# OSC.net
KiCad netlist of a schematic drawn in EAGLE
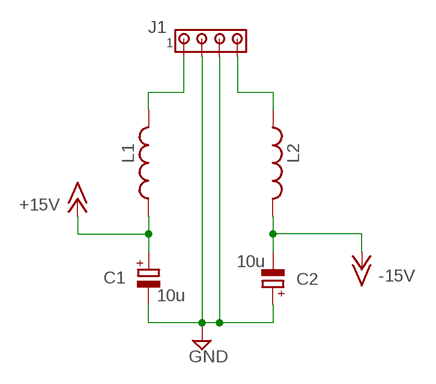
[diagram p0: schematic, sheet 1]
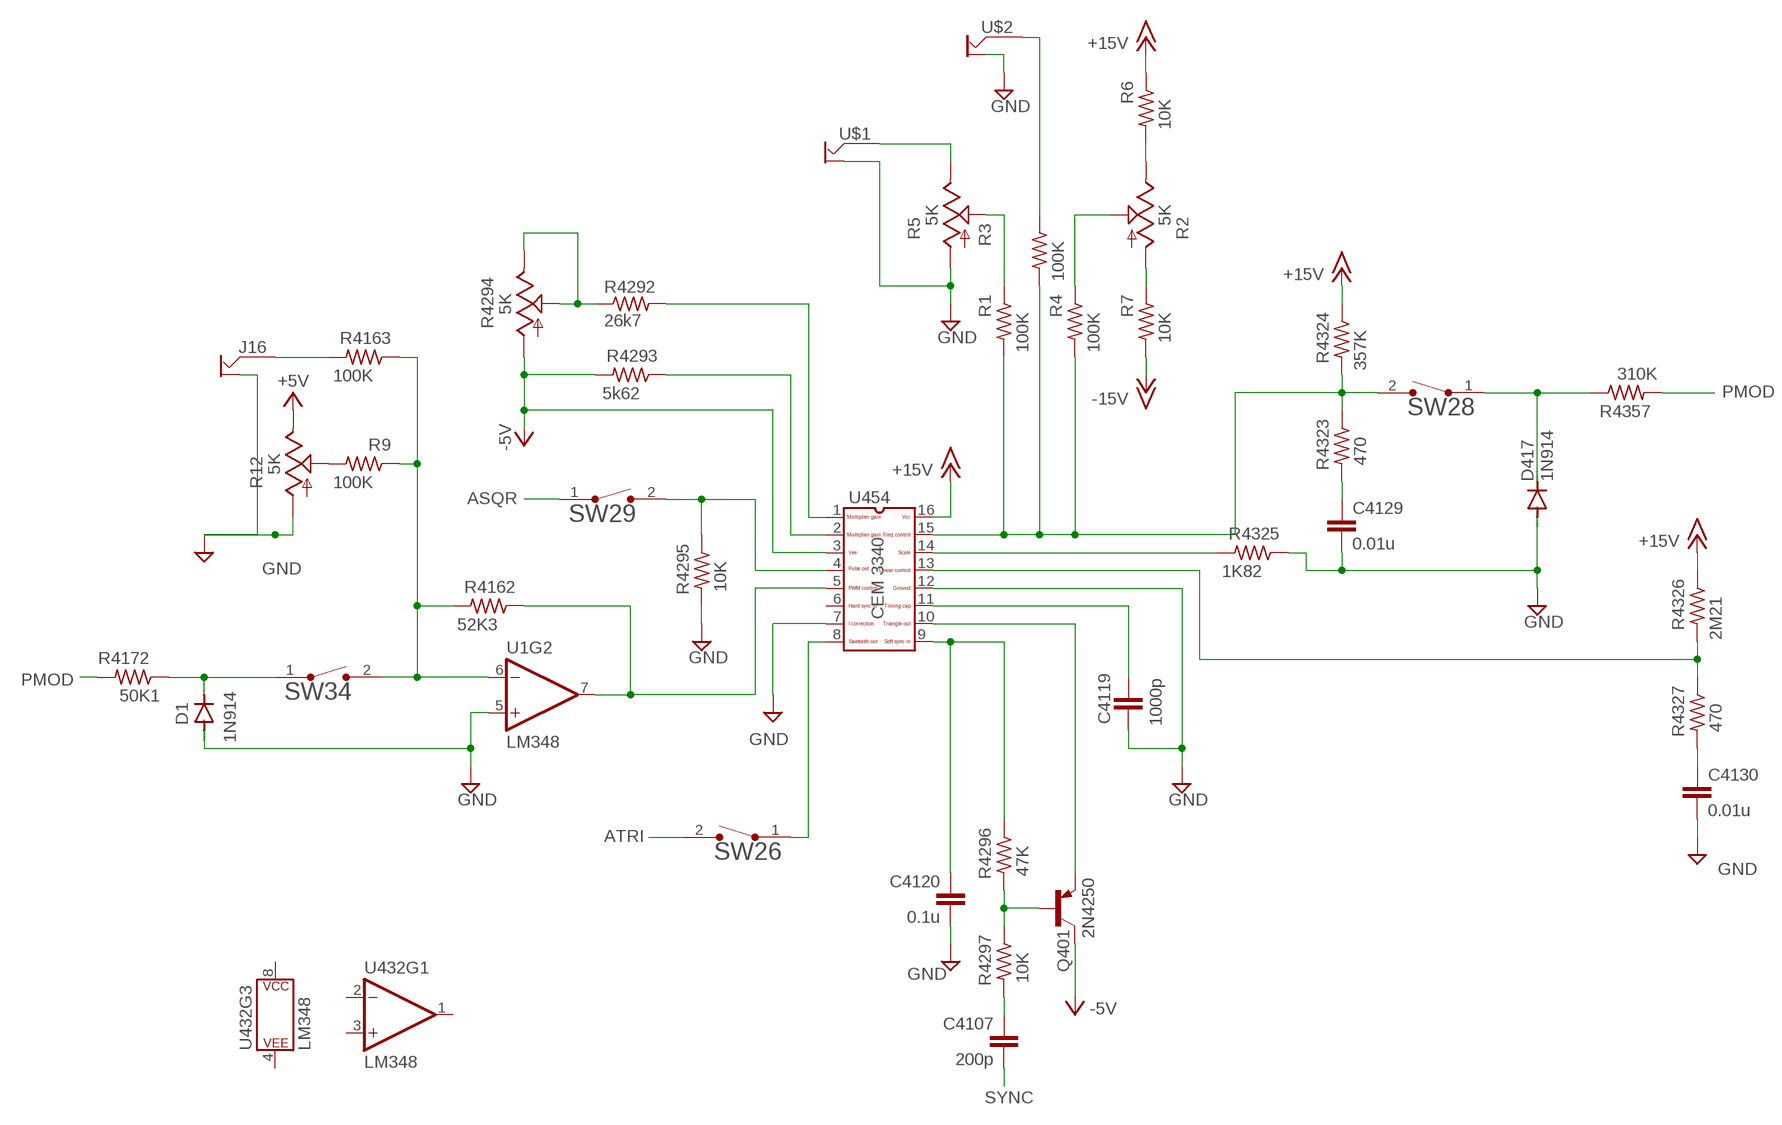
[diagram p1: schematic, sheet 2]
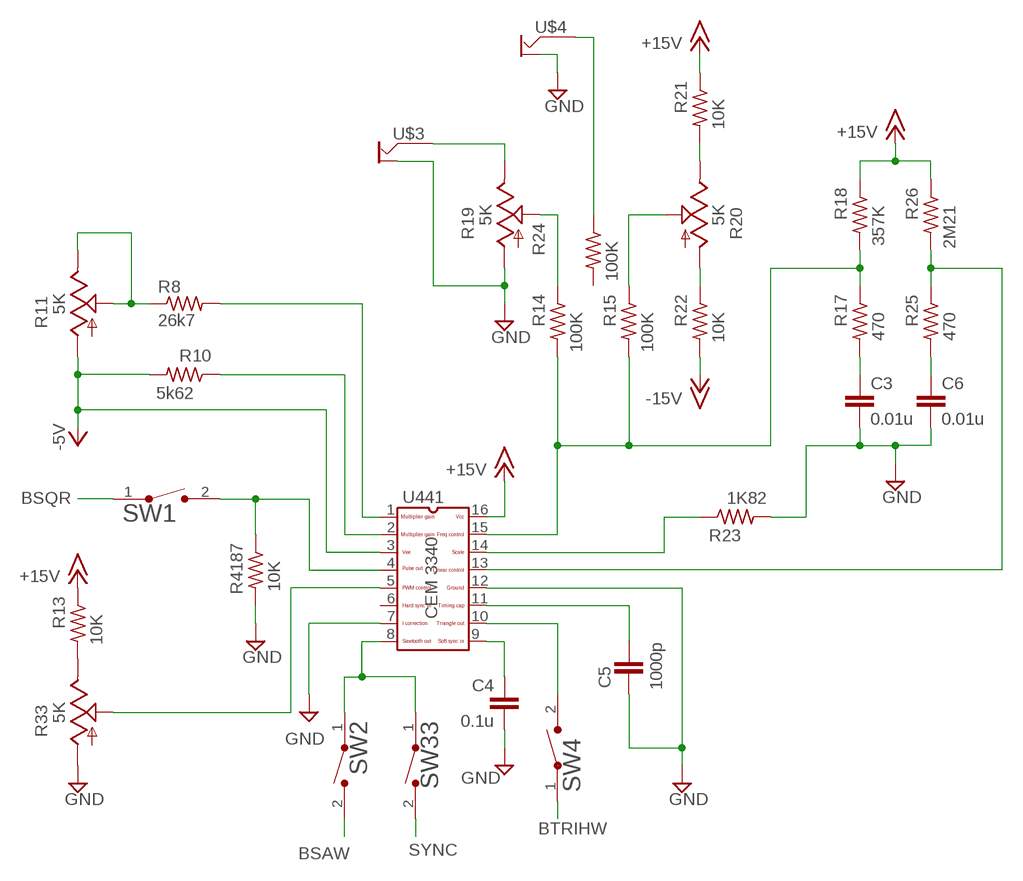
[diagram p2: schematic, sheet 3]
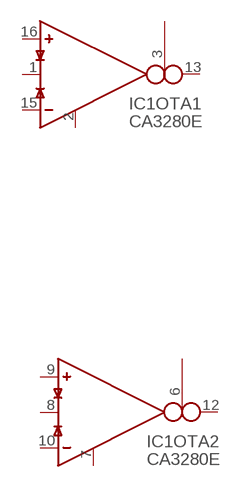
[diagram p3: schematic, sheet 4]

(export (version "E")
  (design (tool "Eeschema 10.0.6"))
  (components
    (comp (ref "C3")
      (value "0.01u")
      (footprint "eagle-import:C050-025X075")
      (libsource (lib "eagle-import") (part "C-EU050-025X075"))
    )
    (comp (ref "C4")
      (value "0.1u")
      (footprint "eagle-import:C050-025X075")
      (libsource (lib "eagle-import") (part "C-EU050-025X075"))
    )
    (comp (ref "C5")
      (value "1000p")
      (footprint "eagle-import:C050-025X075")
      (libsource (lib "eagle-import") (part "C-EU050-025X075"))
    )
    (comp (ref "C6")
      (value "0.01u")
      (footprint "eagle-import:C050-025X075")
      (libsource (lib "eagle-import") (part "C-EU050-025X075"))
    )
    (comp (ref "R8")
      (value "26k7")
      (footprint "eagle-import:0207_10")
      (libsource (lib "eagle-import") (part "R-US_0207/10"))
    )
    (comp (ref "R10")
      (value "5k62")
      (footprint "eagle-import:0207_10")
      (fields (field (name "SPICEPREFIX") "R"))
      (libsource (lib "eagle-import") (part "R-US_0207/10"))
    )
    (comp (ref "R11")
      (value "5K")
      (footprint "eagle-import:POT_OB")
      (libsource (lib "eagle-import") (part "POT"))
    )
    (comp (ref "R13")
      (value "10K")
      (footprint "eagle-import:0207_10")
      (fields (field (name "SPICEPREFIX") "R"))
      (libsource (lib "eagle-import") (part "R-US_0207/10"))
    )
    (comp (ref "R14")
      (value "100K")
      (footprint "eagle-import:0207_10")
      (fields (field (name "SPICEPREFIX") "R"))
      (libsource (lib "eagle-import") (part "R-US_0207/10"))
    )
    (comp (ref "R15")
      (value "100K")
      (footprint "eagle-import:0207_10")
      (fields (field (name "SPICEPREFIX") "R"))
      (libsource (lib "eagle-import") (part "R-US_0207/10"))
    )
    (comp (ref "R17")
      (value "470")
      (footprint "eagle-import:0207_10")
      (fields (field (name "SPICEPREFIX") "R"))
      (libsource (lib "eagle-import") (part "R-US_0207/10"))
    )
    (comp (ref "R18")
      (value "357K")
      (footprint "eagle-import:0207_10")
      (fields (field (name "SPICEPREFIX") "R"))
      (libsource (lib "eagle-import") (part "R-US_0207/10"))
    )
    (comp (ref "R19")
      (value "5K")
      (footprint "eagle-import:POT_OB")
      (libsource (lib "eagle-import") (part "POT"))
    )
    (comp (ref "R20")
      (value "5K")
      (footprint "eagle-import:POT_OB")
      (libsource (lib "eagle-import") (part "POT"))
    )
    (comp (ref "R21")
      (value "10K")
      (footprint "eagle-import:0207_10")
      (fields (field (name "SPICEPREFIX") "R"))
      (libsource (lib "eagle-import") (part "R-US_0207/10"))
    )
    (comp (ref "R22")
      (value "10K")
      (footprint "eagle-import:0207_10")
      (fields (field (name "SPICEPREFIX") "R"))
      (libsource (lib "eagle-import") (part "R-US_0207/10"))
    )
    (comp (ref "R23")
      (value "1K82")
      (footprint "eagle-import:0207_10")
      (fields (field (name "SPICEPREFIX") "R"))
      (libsource (lib "eagle-import") (part "R-US_0207/10"))
    )
    (comp (ref "R24")
      (value "100K")
      (footprint "eagle-import:0207_10")
      (fields (field (name "SPICEPREFIX") "R"))
      (libsource (lib "eagle-import") (part "R-US_0207/10"))
    )
    (comp (ref "R25")
      (value "470")
      (footprint "eagle-import:0207_10")
      (fields (field (name "SPICEPREFIX") "R"))
      (libsource (lib "eagle-import") (part "R-US_0207/10"))
    )
    (comp (ref "R26")
      (value "2M21")
      (footprint "eagle-import:0207_10")
      (fields (field (name "SPICEPREFIX") "R"))
      (libsource (lib "eagle-import") (part "R-US_0207/10"))
    )
    (comp (ref "R33")
      (value "5K")
      (footprint "eagle-import:POT_OB")
      (libsource (lib "eagle-import") (part "POT"))
    )
    (comp (ref "R4187")
      (value "10K")
      (footprint "eagle-import:0207_10")
      (fields (field (name "SPICEPREFIX") "R"))
      (libsource (lib "eagle-import") (part "R-US_0207/10"))
    )
    (comp (ref "SW1")
      (value "SPST")
      (footprint "eagle-import:SPST_OB")
      (libsource (lib "eagle-import") (part "SPST"))
    )
    (comp (ref "SW2")
      (value "SPST")
      (footprint "eagle-import:SPST_OB")
      (libsource (lib "eagle-import") (part "SPST"))
    )
    (comp (ref "SW4")
      (value "SPST")
      (footprint "eagle-import:SPST_OB")
      (libsource (lib "eagle-import") (part "SPST"))
    )
    (comp (ref "SW33")
      (value "SPST")
      (footprint "eagle-import:SPST_OB")
      (libsource (lib "eagle-import") (part "SPST"))
    )
    (comp (ref "U$3")
      (value "JACK")
      (footprint "eagle-import:SIG_OB")
      (libsource (lib "eagle-import") (part "JACK"))
    )
    (comp (ref "U$4")
      (value "JACK")
      (footprint "eagle-import:SIG_OB")
      (libsource (lib "eagle-import") (part "JACK"))
    )
    (comp (ref "U441")
      (value "CEM3340")
      (footprint "eagle-import:DIL16")
      (libsource (lib "eagle-import") (part "CEM3340"))
    )
    (comp (ref "C1")
      (value "10u")
      (footprint "eagle-import:E1,8-4")
      (libsource (lib "eagle-import") (part "CPOL-EUE1.8-4"))
    )
    (comp (ref "C2")
      (value "10u")
      (footprint "eagle-import:E1,8-4")
      (libsource (lib "eagle-import") (part "CPOL-EUE1.8-4"))
    )
    (comp (ref "J1")
      (value "MTA04-156")
      (footprint "eagle-import:1X4MTA")
      (libsource (lib "eagle-import") (part "MTA04-156"))
    )
    (comp (ref "L1")
      (value "L-US0207/10")
      (footprint "eagle-import:0207_10")
      (libsource (lib "eagle-import") (part "L-US0207/10"))
    )
    (comp (ref "L2")
      (value "L-US0207/10")
      (footprint "eagle-import:0207_10")
      (libsource (lib "eagle-import") (part "L-US0207/10"))
    )
    (comp (ref "IC1")
      (value "CA3280E")
      (footprint "eagle-import:DIL16")
      (libsource (lib "eagle-import") (part "CA3280E"))
    )
    (comp (ref "C4107")
      (value "200p")
      (footprint "eagle-import:C050-025X075")
      (libsource (lib "eagle-import") (part "C-EU050-025X075"))
    )
    (comp (ref "C4119")
      (value "1000p")
      (footprint "eagle-import:C050-025X075")
      (libsource (lib "eagle-import") (part "C-EU050-025X075"))
    )
    (comp (ref "C4120")
      (value "0.1u")
      (footprint "eagle-import:C050-025X075")
      (libsource (lib "eagle-import") (part "C-EU050-025X075"))
    )
    (comp (ref "C4129")
      (value "0.01u")
      (footprint "eagle-import:C050-025X075")
      (libsource (lib "eagle-import") (part "C-EU050-025X075"))
    )
    (comp (ref "C4130")
      (value "0.01u")
      (footprint "eagle-import:C050-025X075")
      (libsource (lib "eagle-import") (part "C-EU050-025X075"))
    )
    (comp (ref "D1")
      (value "1N914")
      (footprint "eagle-import:DO35-10")
      (libsource (lib "eagle-import") (part "1N4148DO35-10"))
    )
    (comp (ref "D417")
      (value "1N914")
      (footprint "eagle-import:DO35-10")
      (libsource (lib "eagle-import") (part "1N4148DO35-10"))
    )
    (comp (ref "J16")
      (value "JACK")
      (footprint "eagle-import:SIG_OB")
      (libsource (lib "eagle-import") (part "JACK"))
    )
    (comp (ref "Q401")
      (value "2N4250")
      (footprint "eagle-import:TO18")
      (libsource (lib "eagle-import") (part "2N4250A"))
    )
    (comp (ref "R1")
      (value "100K")
      (footprint "eagle-import:0207_10")
      (fields (field (name "SPICEPREFIX") "R"))
      (libsource (lib "eagle-import") (part "R-US_0207/10"))
    )
    (comp (ref "R2")
      (value "5K")
      (footprint "eagle-import:POT_OB")
      (libsource (lib "eagle-import") (part "POT"))
    )
    (comp (ref "R3")
      (value "100K")
      (footprint "eagle-import:0207_10")
      (fields (field (name "SPICEPREFIX") "R"))
      (libsource (lib "eagle-import") (part "R-US_0207/10"))
    )
    (comp (ref "R4")
      (value "100K")
      (footprint "eagle-import:0207_10")
      (fields (field (name "SPICEPREFIX") "R"))
      (libsource (lib "eagle-import") (part "R-US_0207/10"))
    )
    (comp (ref "R5")
      (value "5K")
      (footprint "eagle-import:POT_OB")
      (libsource (lib "eagle-import") (part "POT"))
    )
    (comp (ref "R6")
      (value "10K")
      (footprint "eagle-import:0207_10")
      (fields (field (name "SPICEPREFIX") "R"))
      (libsource (lib "eagle-import") (part "R-US_0207/10"))
    )
    (comp (ref "R7")
      (value "10K")
      (footprint "eagle-import:0207_10")
      (fields (field (name "SPICEPREFIX") "R"))
      (libsource (lib "eagle-import") (part "R-US_0207/10"))
    )
    (comp (ref "R9")
      (value "100K")
      (footprint "eagle-import:0207_10")
      (fields (field (name "SPICEPREFIX") "R"))
      (libsource (lib "eagle-import") (part "R-US_0207/10"))
    )
    (comp (ref "R12")
      (value "5K")
      (footprint "eagle-import:POT_OB")
      (libsource (lib "eagle-import") (part "POT"))
    )
    (comp (ref "R4162")
      (value "52K3")
      (footprint "eagle-import:0207_10")
      (fields (field (name "SPICEPREFIX") "R"))
      (libsource (lib "eagle-import") (part "R-US_0207/10"))
    )
    (comp (ref "R4163")
      (value "100K")
      (footprint "eagle-import:0207_10")
      (fields (field (name "SPICEPREFIX") "R"))
      (libsource (lib "eagle-import") (part "R-US_0207/10"))
    )
    (comp (ref "R4172")
      (value "50K1")
      (footprint "eagle-import:0207_10")
      (fields (field (name "SPICEPREFIX") "R"))
      (libsource (lib "eagle-import") (part "R-US_0207/10"))
    )
    (comp (ref "R4292")
      (value "26k7")
      (footprint "eagle-import:0207_10")
      (libsource (lib "eagle-import") (part "R-US_0207/10"))
    )
    (comp (ref "R4293")
      (value "5k62")
      (footprint "eagle-import:0207_10")
      (fields (field (name "SPICEPREFIX") "R"))
      (libsource (lib "eagle-import") (part "R-US_0207/10"))
    )
    (comp (ref "R4294")
      (value "5K")
      (footprint "eagle-import:POT_OB")
      (libsource (lib "eagle-import") (part "POT"))
    )
    (comp (ref "R4295")
      (value "10K")
      (footprint "eagle-import:0207_10")
      (fields (field (name "SPICEPREFIX") "R"))
      (libsource (lib "eagle-import") (part "R-US_0207/10"))
    )
    (comp (ref "R4296")
      (value "47K")
      (footprint "eagle-import:0207_10")
      (fields (field (name "SPICEPREFIX") "R"))
      (libsource (lib "eagle-import") (part "R-US_0207/10"))
    )
    (comp (ref "R4297")
      (value "10K")
      (footprint "eagle-import:0207_10")
      (fields (field (name "SPICEPREFIX") "R"))
      (libsource (lib "eagle-import") (part "R-US_0207/10"))
    )
    (comp (ref "R4323")
      (value "470")
      (footprint "eagle-import:0207_10")
      (fields (field (name "SPICEPREFIX") "R"))
      (libsource (lib "eagle-import") (part "R-US_0207/10"))
    )
    (comp (ref "R4324")
      (value "357K")
      (footprint "eagle-import:0207_10")
      (fields (field (name "SPICEPREFIX") "R"))
      (libsource (lib "eagle-import") (part "R-US_0207/10"))
    )
    (comp (ref "R4325")
      (value "1K82")
      (footprint "eagle-import:0207_10")
      (fields (field (name "SPICEPREFIX") "R"))
      (libsource (lib "eagle-import") (part "R-US_0207/10"))
    )
    (comp (ref "R4326")
      (value "2M21")
      (footprint "eagle-import:0207_10")
      (fields (field (name "SPICEPREFIX") "R"))
      (libsource (lib "eagle-import") (part "R-US_0207/10"))
    )
    (comp (ref "R4327")
      (value "470")
      (footprint "eagle-import:0207_10")
      (fields (field (name "SPICEPREFIX") "R"))
      (libsource (lib "eagle-import") (part "R-US_0207/10"))
    )
    (comp (ref "R4357")
      (value "310K")
      (footprint "eagle-import:0207_10")
      (fields (field (name "SPICEPREFIX") "R"))
      (libsource (lib "eagle-import") (part "R-US_0207/10"))
    )
    (comp (ref "SW26")
      (value "SPST")
      (footprint "eagle-import:SPST_OB")
      (libsource (lib "eagle-import") (part "SPST"))
    )
    (comp (ref "SW28")
      (value "SPST")
      (footprint "eagle-import:SPST_OB")
      (libsource (lib "eagle-import") (part "SPST"))
    )
    (comp (ref "SW29")
      (value "SPST")
      (footprint "eagle-import:SPST_OB")
      (libsource (lib "eagle-import") (part "SPST"))
    )
    (comp (ref "SW34")
      (value "SPST")
      (footprint "eagle-import:SPST_OB")
      (libsource (lib "eagle-import") (part "SPST"))
    )
    (comp (ref "U$1")
      (value "JACK")
      (footprint "eagle-import:SIG_OB")
      (libsource (lib "eagle-import") (part "JACK"))
    )
    (comp (ref "U$2")
      (value "JACK")
      (footprint "eagle-import:SIG_OB")
      (libsource (lib "eagle-import") (part "JACK"))
    )
    (comp (ref "U1")
      (value "LM348")
      (footprint "eagle-import:DIP08")
      (libsource (lib "eagle-import") (part "LM358"))
    )
    (comp (ref "U432")
      (value "LM348")
      (footprint "eagle-import:DIP08")
      (libsource (lib "eagle-import") (part "LM358"))
    )
    (comp (ref "U454")
      (value "CEM3340")
      (footprint "eagle-import:DIL16")
      (libsource (lib "eagle-import") (part "CEM3340"))
    )
  )
  (nets
    (net (code "1") (name "+5V") (class "Default")
      (node (ref "R12") (pin "2") (pinfunction "E_2") (pintype "passive"))
    )
    (net (code "2") (name "+15V") (class "Default")
      (node (ref "C1") (pin "+") (pinfunction "+_+") (pintype "passive"))
      (node (ref "L1") (pin "2") (pinfunction "2_2") (pintype "passive"))
      (node (ref "R13") (pin "1") (pinfunction "1_1") (pintype "passive"))
      (node (ref "R18") (pin "1") (pinfunction "1_1") (pintype "passive"))
      (node (ref "R21") (pin "1") (pinfunction "1_1") (pintype "passive"))
      (node (ref "R26") (pin "1") (pinfunction "1_1") (pintype "passive"))
      (node (ref "R4324") (pin "1") (pinfunction "1_1") (pintype "passive"))
      (node (ref "R4326") (pin "1") (pinfunction "1_1") (pintype "passive"))
      (node (ref "R6") (pin "1") (pinfunction "1_1") (pintype "passive"))
      (node (ref "U441") (pin "16") (pinfunction "16_16") (pintype "power_in"))
      (node (ref "U454") (pin "16") (pinfunction "16_16") (pintype "power_in"))
    )
    (net (code "3") (name "-5V") (class "Default")
      (node (ref "Q401") (pin "3") (pinfunction "C_3") (pintype "passive"))
      (node (ref "R10") (pin "2") (pinfunction "2_2") (pintype "passive"))
      (node (ref "R11") (pin "1") (pinfunction "A_1") (pintype "passive"))
      (node (ref "R4293") (pin "2") (pinfunction "2_2") (pintype "passive"))
      (node (ref "R4294") (pin "1") (pinfunction "A_1") (pintype "passive"))
      (node (ref "U441") (pin "3") (pinfunction "3_3") (pintype "power_in"))
      (node (ref "U454") (pin "3") (pinfunction "3_3") (pintype "power_in"))
    )
    (net (code "4") (name "-15V") (class "Default")
      (node (ref "C2") (pin "-") (pinfunction "-_-") (pintype "passive"))
      (node (ref "L2") (pin "2") (pinfunction "2_2") (pintype "passive"))
      (node (ref "R22") (pin "2") (pinfunction "2_2") (pintype "passive"))
      (node (ref "R7") (pin "2") (pinfunction "2_2") (pintype "passive"))
    )
    (net (code "5") (name "ASQR") (class "Default")
      (node (ref "SW29") (pin "1") (pinfunction "1_1") (pintype "passive"))
    )
    (net (code "6") (name "ATRI") (class "Default")
      (node (ref "SW26") (pin "2") (pinfunction "2_2") (pintype "passive"))
    )
    (net (code "7") (name "BSAW") (class "Default")
      (node (ref "SW2") (pin "2") (pinfunction "2_2") (pintype "passive"))
    )
    (net (code "8") (name "BSQR") (class "Default")
      (node (ref "SW1") (pin "1") (pinfunction "1_1") (pintype "passive"))
    )
    (net (code "9") (name "BTRIHW") (class "Default")
      (node (ref "SW4") (pin "1") (pinfunction "1_1") (pintype "passive"))
    )
    (net (code "10") (name "GND") (class "Default")
      (node (ref "C1") (pin "-") (pinfunction "-_-") (pintype "passive"))
      (node (ref "C2") (pin "+") (pinfunction "+_+") (pintype "passive"))
      (node (ref "C3") (pin "2") (pinfunction "2_2") (pintype "passive"))
      (node (ref "C4") (pin "2") (pinfunction "2_2") (pintype "passive"))
      (node (ref "C4119") (pin "2") (pinfunction "2_2") (pintype "passive"))
      (node (ref "C4120") (pin "2") (pinfunction "2_2") (pintype "passive"))
      (node (ref "C4129") (pin "2") (pinfunction "2_2") (pintype "passive"))
      (node (ref "C4130") (pin "2") (pinfunction "2_2") (pintype "passive"))
      (node (ref "C5") (pin "2") (pinfunction "2_2") (pintype "passive"))
      (node (ref "C6") (pin "2") (pinfunction "2_2") (pintype "passive"))
      (node (ref "D1") (pin "A") (pinfunction "A_A") (pintype "passive"))
      (node (ref "D417") (pin "A") (pinfunction "A_A") (pintype "passive"))
      (node (ref "J1") (pin "2") (pinfunction "2_2") (pintype "passive"))
      (node (ref "J1") (pin "3") (pinfunction "3_3") (pintype "passive"))
      (node (ref "J16") (pin "GND") (pinfunction "GND_GND") (pintype "passive"))
      (node (ref "R12") (pin "1") (pinfunction "A_1") (pintype "passive"))
      (node (ref "R19") (pin "1") (pinfunction "A_1") (pintype "passive"))
      (node (ref "R23") (pin "2") (pinfunction "2_2") (pintype "passive"))
      (node (ref "R33") (pin "1") (pinfunction "A_1") (pintype "passive"))
      (node (ref "R4187") (pin "2") (pinfunction "2_2") (pintype "passive"))
      (node (ref "R4295") (pin "2") (pinfunction "2_2") (pintype "passive"))
      (node (ref "R4325") (pin "1") (pinfunction "1_1") (pintype "passive"))
      (node (ref "R5") (pin "1") (pinfunction "A_1") (pintype "passive"))
      (node (ref "U$1") (pin "GND") (pinfunction "GND_GND") (pintype "passive"))
      (node (ref "U$2") (pin "GND") (pinfunction "GND_GND") (pintype "passive"))
      (node (ref "U$3") (pin "GND") (pinfunction "GND_GND") (pintype "passive"))
      (node (ref "U$4") (pin "GND") (pinfunction "GND_GND") (pintype "passive"))
      (node (ref "U1") (pin "5") (pinfunction "+IN_5") (pintype "input"))
      (node (ref "U441") (pin "12") (pinfunction "12_12") (pintype "power_in"))
      (node (ref "U441") (pin "7") (pinfunction "7_7") (pintype "bidirectional"))
      (node (ref "U454") (pin "12") (pinfunction "12_12") (pintype "power_in"))
      (node (ref "U454") (pin "7") (pinfunction "7_7") (pintype "bidirectional"))
    )
    (net (code "11") (name "Net-(C3-Pad1)") (class "Default")
      (node (ref "C3") (pin "1") (pinfunction "1_1") (pintype "passive"))
      (node (ref "R17") (pin "2") (pinfunction "2_2") (pintype "passive"))
    )
    (net (code "12") (name "Net-(C4-Pad1)") (class "Default")
      (node (ref "C4") (pin "1") (pinfunction "1_1") (pintype "passive"))
      (node (ref "U441") (pin "9") (pinfunction "9_9") (pintype "input"))
    )
    (net (code "13") (name "Net-(C5-Pad1)") (class "Default")
      (node (ref "C5") (pin "1") (pinfunction "1_1") (pintype "passive"))
      (node (ref "U441") (pin "11") (pinfunction "11_11") (pintype "bidirectional"))
    )
    (net (code "14") (name "Net-(C6-Pad1)") (class "Default")
      (node (ref "C6") (pin "1") (pinfunction "1_1") (pintype "passive"))
      (node (ref "R25") (pin "2") (pinfunction "2_2") (pintype "passive"))
    )
    (net (code "15") (name "Net-(C4107-Pad1)") (class "Default")
      (node (ref "C4107") (pin "1") (pinfunction "1_1") (pintype "passive"))
      (node (ref "R4297") (pin "2") (pinfunction "2_2") (pintype "passive"))
    )
    (net (code "16") (name "Net-(C4119-Pad1)") (class "Default")
      (node (ref "C4119") (pin "1") (pinfunction "1_1") (pintype "passive"))
      (node (ref "U454") (pin "11") (pinfunction "11_11") (pintype "bidirectional"))
    )
    (net (code "17") (name "Net-(C4120-Pad1)") (class "Default")
      (node (ref "C4120") (pin "1") (pinfunction "1_1") (pintype "passive"))
      (node (ref "R4296") (pin "1") (pinfunction "1_1") (pintype "passive"))
      (node (ref "U454") (pin "9") (pinfunction "9_9") (pintype "input"))
    )
    (net (code "18") (name "Net-(C4129-Pad1)") (class "Default")
      (node (ref "C4129") (pin "1") (pinfunction "1_1") (pintype "passive"))
      (node (ref "R4323") (pin "2") (pinfunction "2_2") (pintype "passive"))
    )
    (net (code "19") (name "Net-(C4130-Pad1)") (class "Default")
      (node (ref "C4130") (pin "1") (pinfunction "1_1") (pintype "passive"))
      (node (ref "R4327") (pin "2") (pinfunction "2_2") (pintype "passive"))
    )
    (net (code "20") (name "Net-(D1-PadC)") (class "Default")
      (node (ref "D1") (pin "C") (pinfunction "C_C") (pintype "passive"))
      (node (ref "R4172") (pin "1") (pinfunction "1_1") (pintype "passive"))
      (node (ref "SW34") (pin "1") (pinfunction "1_1") (pintype "passive"))
    )
    (net (code "21") (name "Net-(D417-PadC)") (class "Default")
      (node (ref "D417") (pin "C") (pinfunction "C_C") (pintype "passive"))
      (node (ref "R4357") (pin "1") (pinfunction "1_1") (pintype "passive"))
      (node (ref "SW28") (pin "1") (pinfunction "1_1") (pintype "passive"))
    )
    (net (code "22") (name "Net-(J1-Pad1)") (class "Default")
      (node (ref "J1") (pin "1") (pinfunction "1_1") (pintype "passive"))
      (node (ref "L1") (pin "1") (pinfunction "1_1") (pintype "passive"))
    )
    (net (code "23") (name "Net-(J1-Pad4)") (class "Default")
      (node (ref "J1") (pin "4") (pinfunction "4_4") (pintype "passive"))
      (node (ref "L2") (pin "1") (pinfunction "1_1") (pintype "passive"))
    )
    (net (code "24") (name "Net-(J16-PadSIGNAL)") (class "Default")
      (node (ref "J16") (pin "SIGNAL") (pinfunction "SIGNAL_SIGNAL") (pintype "passive"))
      (node (ref "R4163") (pin "2") (pinfunction "2_2") (pintype "passive"))
    )
    (net (code "25") (name "Net-(Q401-B)") (class "Default")
      (node (ref "Q401") (pin "2") (pinfunction "B_2") (pintype "passive"))
      (node (ref "R4296") (pin "2") (pinfunction "2_2") (pintype "passive"))
      (node (ref "R4297") (pin "1") (pinfunction "1_1") (pintype "passive"))
    )
    (net (code "26") (name "Net-(Q401-E)") (class "Default")
      (node (ref "Q401") (pin "1") (pinfunction "E_1") (pintype "passive"))
      (node (ref "U454") (pin "10") (pinfunction "10_10") (pintype "output"))
    )
    (net (code "27") (name "Net-(R1-Pad2)") (class "Default")
      (node (ref "R1") (pin "2") (pinfunction "2_2") (pintype "passive"))
      (node (ref "R3") (pin "2") (pinfunction "2_2") (pintype "passive"))
      (node (ref "R4") (pin "2") (pinfunction "2_2") (pintype "passive"))
      (node (ref "R4323") (pin "1") (pinfunction "1_1") (pintype "passive"))
      (node (ref "R4324") (pin "2") (pinfunction "2_2") (pintype "passive"))
      (node (ref "SW28") (pin "2") (pinfunction "2_2") (pintype "passive"))
      (node (ref "U454") (pin "15") (pinfunction "15_15") (pintype "input"))
    )
    (net (code "28") (name "Net-(R2-A)") (class "Default")
      (node (ref "R2") (pin "1") (pinfunction "A_1") (pintype "passive"))
      (node (ref "R7") (pin "1") (pinfunction "1_1") (pintype "passive"))
    )
    (net (code "29") (name "Net-(R2-E)") (class "Default")
      (node (ref "R2") (pin "2") (pinfunction "E_2") (pintype "passive"))
      (node (ref "R6") (pin "2") (pinfunction "2_2") (pintype "passive"))
    )
    (net (code "30") (name "Net-(R2-S)") (class "Default")
      (node (ref "R2") (pin "3") (pinfunction "S_3") (pintype "passive"))
      (node (ref "R4") (pin "1") (pinfunction "1_1") (pintype "passive"))
    )
    (net (code "31") (name "Net-(R3-Pad1)") (class "Default")
      (node (ref "R3") (pin "1") (pinfunction "1_1") (pintype "passive"))
      (node (ref "U$2") (pin "SIGNAL") (pinfunction "SIGNAL_SIGNAL") (pintype "passive"))
    )
    (net (code "32") (name "Net-(R5-E)") (class "Default")
      (node (ref "R5") (pin "2") (pinfunction "E_2") (pintype "passive"))
      (node (ref "U$1") (pin "SIGNAL") (pinfunction "SIGNAL_SIGNAL") (pintype "passive"))
    )
    (net (code "33") (name "Net-(R5-S)") (class "Default")
      (node (ref "R1") (pin "1") (pinfunction "1_1") (pintype "passive"))
      (node (ref "R5") (pin "3") (pinfunction "S_3") (pintype "passive"))
    )
    (net (code "34") (name "Net-(R8-Pad2)") (class "Default")
      (node (ref "R8") (pin "2") (pinfunction "2_2") (pintype "passive"))
      (node (ref "U441") (pin "1") (pinfunction "1_1") (pintype "bidirectional"))
    )
    (net (code "35") (name "Net-(R10-Pad1)") (class "Default")
      (node (ref "R10") (pin "1") (pinfunction "1_1") (pintype "passive"))
      (node (ref "U441") (pin "2") (pinfunction "2_2") (pintype "bidirectional"))
    )
    (net (code "36") (name "Net-(R11-E)") (class "Default")
      (node (ref "R11") (pin "2") (pinfunction "E_2") (pintype "passive"))
      (node (ref "R11") (pin "3") (pinfunction "S_3") (pintype "passive"))
      (node (ref "R8") (pin "1") (pinfunction "1_1") (pintype "passive"))
    )
    (net (code "37") (name "Net-(R12-S)") (class "Default")
      (node (ref "R12") (pin "3") (pinfunction "S_3") (pintype "passive"))
      (node (ref "R9") (pin "2") (pinfunction "2_2") (pintype "passive"))
    )
    (net (code "38") (name "Net-(R14-Pad2)") (class "Default")
      (node (ref "R14") (pin "2") (pinfunction "2_2") (pintype "passive"))
      (node (ref "R15") (pin "2") (pinfunction "2_2") (pintype "passive"))
      (node (ref "R17") (pin "1") (pinfunction "1_1") (pintype "passive"))
      (node (ref "R18") (pin "2") (pinfunction "2_2") (pintype "passive"))
      (node (ref "U441") (pin "15") (pinfunction "15_15") (pintype "input"))
    )
    (net (code "39") (name "Net-(R19-E)") (class "Default")
      (node (ref "R19") (pin "2") (pinfunction "E_2") (pintype "passive"))
      (node (ref "U$3") (pin "SIGNAL") (pinfunction "SIGNAL_SIGNAL") (pintype "passive"))
    )
    (net (code "40") (name "Net-(R19-S)") (class "Default")
      (node (ref "R14") (pin "1") (pinfunction "1_1") (pintype "passive"))
      (node (ref "R19") (pin "3") (pinfunction "S_3") (pintype "passive"))
    )
    (net (code "41") (name "Net-(R20-A)") (class "Default")
      (node (ref "R20") (pin "1") (pinfunction "A_1") (pintype "passive"))
      (node (ref "R22") (pin "1") (pinfunction "1_1") (pintype "passive"))
    )
    (net (code "42") (name "Net-(R20-E)") (class "Default")
      (node (ref "R20") (pin "2") (pinfunction "E_2") (pintype "passive"))
      (node (ref "R21") (pin "2") (pinfunction "2_2") (pintype "passive"))
    )
    (net (code "43") (name "Net-(R20-S)") (class "Default")
      (node (ref "R15") (pin "1") (pinfunction "1_1") (pintype "passive"))
      (node (ref "R20") (pin "3") (pinfunction "S_3") (pintype "passive"))
    )
    (net (code "44") (name "Net-(R23-Pad1)") (class "Default")
      (node (ref "R23") (pin "1") (pinfunction "1_1") (pintype "passive"))
      (node (ref "U441") (pin "14") (pinfunction "14_14") (pintype "input"))
    )
    (net (code "45") (name "Net-(R24-Pad1)") (class "Default")
      (node (ref "R24") (pin "1") (pinfunction "1_1") (pintype "passive"))
      (node (ref "U$4") (pin "SIGNAL") (pinfunction "SIGNAL_SIGNAL") (pintype "passive"))
    )
    (net (code "46") (name "Net-(R25-Pad1)") (class "Default")
      (node (ref "R25") (pin "1") (pinfunction "1_1") (pintype "passive"))
      (node (ref "R26") (pin "2") (pinfunction "2_2") (pintype "passive"))
      (node (ref "U441") (pin "13") (pinfunction "13_13") (pintype "input"))
    )
    (net (code "47") (name "Net-(R33-E)") (class "Default")
      (node (ref "R13") (pin "2") (pinfunction "2_2") (pintype "passive"))
      (node (ref "R33") (pin "2") (pinfunction "E_2") (pintype "passive"))
    )
    (net (code "48") (name "Net-(R33-S)") (class "Default")
      (node (ref "R33") (pin "3") (pinfunction "S_3") (pintype "passive"))
      (node (ref "U441") (pin "5") (pinfunction "5_5") (pintype "input"))
    )
    (net (code "49") (name "Net-(R4187-Pad1)") (class "Default")
      (node (ref "R4187") (pin "1") (pinfunction "1_1") (pintype "passive"))
      (node (ref "SW1") (pin "2") (pinfunction "2_2") (pintype "passive"))
      (node (ref "U441") (pin "4") (pinfunction "4_4") (pintype "output"))
    )
    (net (code "50") (name "Net-(R4292-Pad2)") (class "Default")
      (node (ref "R4292") (pin "2") (pinfunction "2_2") (pintype "passive"))
      (node (ref "U454") (pin "1") (pinfunction "1_1") (pintype "bidirectional"))
    )
    (net (code "51") (name "Net-(R4293-Pad1)") (class "Default")
      (node (ref "R4293") (pin "1") (pinfunction "1_1") (pintype "passive"))
      (node (ref "U454") (pin "2") (pinfunction "2_2") (pintype "bidirectional"))
    )
    (net (code "52") (name "Net-(R4294-E)") (class "Default")
      (node (ref "R4292") (pin "1") (pinfunction "1_1") (pintype "passive"))
      (node (ref "R4294") (pin "2") (pinfunction "E_2") (pintype "passive"))
      (node (ref "R4294") (pin "3") (pinfunction "S_3") (pintype "passive"))
    )
    (net (code "53") (name "Net-(R4295-Pad1)") (class "Default")
      (node (ref "R4295") (pin "1") (pinfunction "1_1") (pintype "passive"))
      (node (ref "SW29") (pin "2") (pinfunction "2_2") (pintype "passive"))
      (node (ref "U454") (pin "4") (pinfunction "4_4") (pintype "output"))
    )
    (net (code "54") (name "Net-(R4325-Pad2)") (class "Default")
      (node (ref "R4325") (pin "2") (pinfunction "2_2") (pintype "passive"))
      (node (ref "U454") (pin "14") (pinfunction "14_14") (pintype "input"))
    )
    (net (code "55") (name "Net-(R4326-Pad2)") (class "Default")
      (node (ref "R4326") (pin "2") (pinfunction "2_2") (pintype "passive"))
      (node (ref "R4327") (pin "1") (pinfunction "1_1") (pintype "passive"))
      (node (ref "U454") (pin "13") (pinfunction "13_13") (pintype "input"))
    )
    (net (code "56") (name "Net-(SW2-Pad1)") (class "Default")
      (node (ref "SW2") (pin "1") (pinfunction "1_1") (pintype "passive"))
      (node (ref "SW33") (pin "1") (pinfunction "1_1") (pintype "passive"))
      (node (ref "U441") (pin "8") (pinfunction "8_8") (pintype "output"))
    )
    (net (code "57") (name "Net-(SW4-Pad2)") (class "Default")
      (node (ref "SW4") (pin "2") (pinfunction "2_2") (pintype "passive"))
      (node (ref "U441") (pin "10") (pinfunction "10_10") (pintype "output"))
    )
    (net (code "58") (name "Net-(SW26-Pad1)") (class "Default")
      (node (ref "SW26") (pin "1") (pinfunction "1_1") (pintype "passive"))
      (node (ref "U454") (pin "8") (pinfunction "8_8") (pintype "output"))
    )
    (net (code "59") (name "Net-(U1B--IN)") (class "Default")
      (node (ref "R4162") (pin "2") (pinfunction "2_2") (pintype "passive"))
      (node (ref "R4163") (pin "1") (pinfunction "1_1") (pintype "passive"))
      (node (ref "R9") (pin "1") (pinfunction "1_1") (pintype "passive"))
      (node (ref "SW34") (pin "2") (pinfunction "2_2") (pintype "passive"))
      (node (ref "U1") (pin "6") (pinfunction "-IN_6") (pintype "input"))
    )
    (net (code "60") (name "Net-(U1B-OUT)") (class "Default")
      (node (ref "R4162") (pin "1") (pinfunction "1_1") (pintype "passive"))
      (node (ref "U1") (pin "7") (pinfunction "OUT_7") (pintype "output"))
      (node (ref "U454") (pin "5") (pinfunction "5_5") (pintype "input"))
    )
    (net (code "61") (name "PMOD") (class "Default")
      (node (ref "R4172") (pin "2") (pinfunction "2_2") (pintype "passive"))
      (node (ref "R4357") (pin "2") (pinfunction "2_2") (pintype "passive"))
    )
    (net (code "62") (name "SYNC") (class "Default")
      (node (ref "C4107") (pin "2") (pinfunction "2_2") (pintype "passive"))
      (node (ref "SW33") (pin "2") (pinfunction "2_2") (pintype "passive"))
    )
    (net (code "63") (name "unconnected-(IC1A-IN_N-Pad15)") (class "Default")
      (node (ref "IC1") (pin "15") (pinfunction "IN_N_15") (pintype "input"))
    )
    (net (code "64") (name "unconnected-(IC1A-IN_P-Pad16)") (class "Default")
      (node (ref "IC1") (pin "16") (pinfunction "IN_P_16") (pintype "input"))
    )
    (net (code "65") (name "unconnected-(IC1A-I_BIAS-Pad3)") (class "Default")
      (node (ref "IC1") (pin "3") (pinfunction "I_BIAS_3") (pintype "input"))
    )
    (net (code "66") (name "unconnected-(IC1A-I_DIODE-Pad1)") (class "Default")
      (node (ref "IC1") (pin "1") (pinfunction "I_DIODE_1") (pintype "input"))
    )
    (net (code "67") (name "unconnected-(IC1A-NODE_X-Pad2)") (class "Default")
      (node (ref "IC1") (pin "2") (pinfunction "NODE_X_2") (pintype "input"))
    )
    (net (code "68") (name "unconnected-(IC1A-OUT-Pad13)") (class "Default")
      (node (ref "IC1") (pin "13") (pinfunction "OUT_13") (pintype "output"))
    )
    (net (code "69") (name "unconnected-(IC1B-IN_N-Pad10)") (class "Default")
      (node (ref "IC1") (pin "10") (pinfunction "IN_N_10") (pintype "input"))
    )
    (net (code "70") (name "unconnected-(IC1B-IN_P-Pad9)") (class "Default")
      (node (ref "IC1") (pin "9") (pinfunction "IN_P_9") (pintype "input"))
    )
    (net (code "71") (name "unconnected-(IC1B-I_BIAS-Pad6)") (class "Default")
      (node (ref "IC1") (pin "6") (pinfunction "I_BIAS_6") (pintype "input"))
    )
    (net (code "72") (name "unconnected-(IC1B-I_DIODE-Pad8)") (class "Default")
      (node (ref "IC1") (pin "8") (pinfunction "I_DIODE_8") (pintype "input"))
    )
    (net (code "73") (name "unconnected-(IC1B-NODE_X-Pad7)") (class "Default")
      (node (ref "IC1") (pin "7") (pinfunction "NODE_X_7") (pintype "input"))
    )
    (net (code "74") (name "unconnected-(IC1B-OUT-Pad12)") (class "Default")
      (node (ref "IC1") (pin "12") (pinfunction "OUT_12") (pintype "output"))
    )
    (net (code "75") (name "unconnected-(R24-Pad2)") (class "Default")
      (node (ref "R24") (pin "2") (pinfunction "2_2") (pintype "passive"))
    )
    (net (code "76") (name "unconnected-(U432A-+IN-Pad3)") (class "Default")
      (node (ref "U432") (pin "3") (pinfunction "+IN_3") (pintype "input"))
    )
    (net (code "77") (name "unconnected-(U432A--IN-Pad2)") (class "Default")
      (node (ref "U432") (pin "2") (pinfunction "-IN_2") (pintype "input"))
    )
    (net (code "78") (name "unconnected-(U432A-OUT-Pad1)") (class "Default")
      (node (ref "U432") (pin "1") (pinfunction "OUT_1") (pintype "output"))
    )
    (net (code "79") (name "unconnected-(U432C-P$V+-Pad8)") (class "Default")
      (node (ref "U432") (pin "8") (pinfunction "P$V+_8") (pintype "bidirectional"))
    )
    (net (code "80") (name "unconnected-(U432C-P$V--Pad4)") (class "Default")
      (node (ref "U432") (pin "4") (pinfunction "P$V-_4") (pintype "bidirectional"))
    )
    (net (code "81") (name "unconnected-(U441-Pad6)") (class "Default")
      (node (ref "U441") (pin "6") (pinfunction "6_6") (pintype "input"))
    )
    (net (code "82") (name "unconnected-(U454-Pad6)") (class "Default")
      (node (ref "U454") (pin "6") (pinfunction "6_6") (pintype "input"))
    )
  )
)
